# 06_rng.net
KiCad netlist of a schematic drawn in Altium Designer
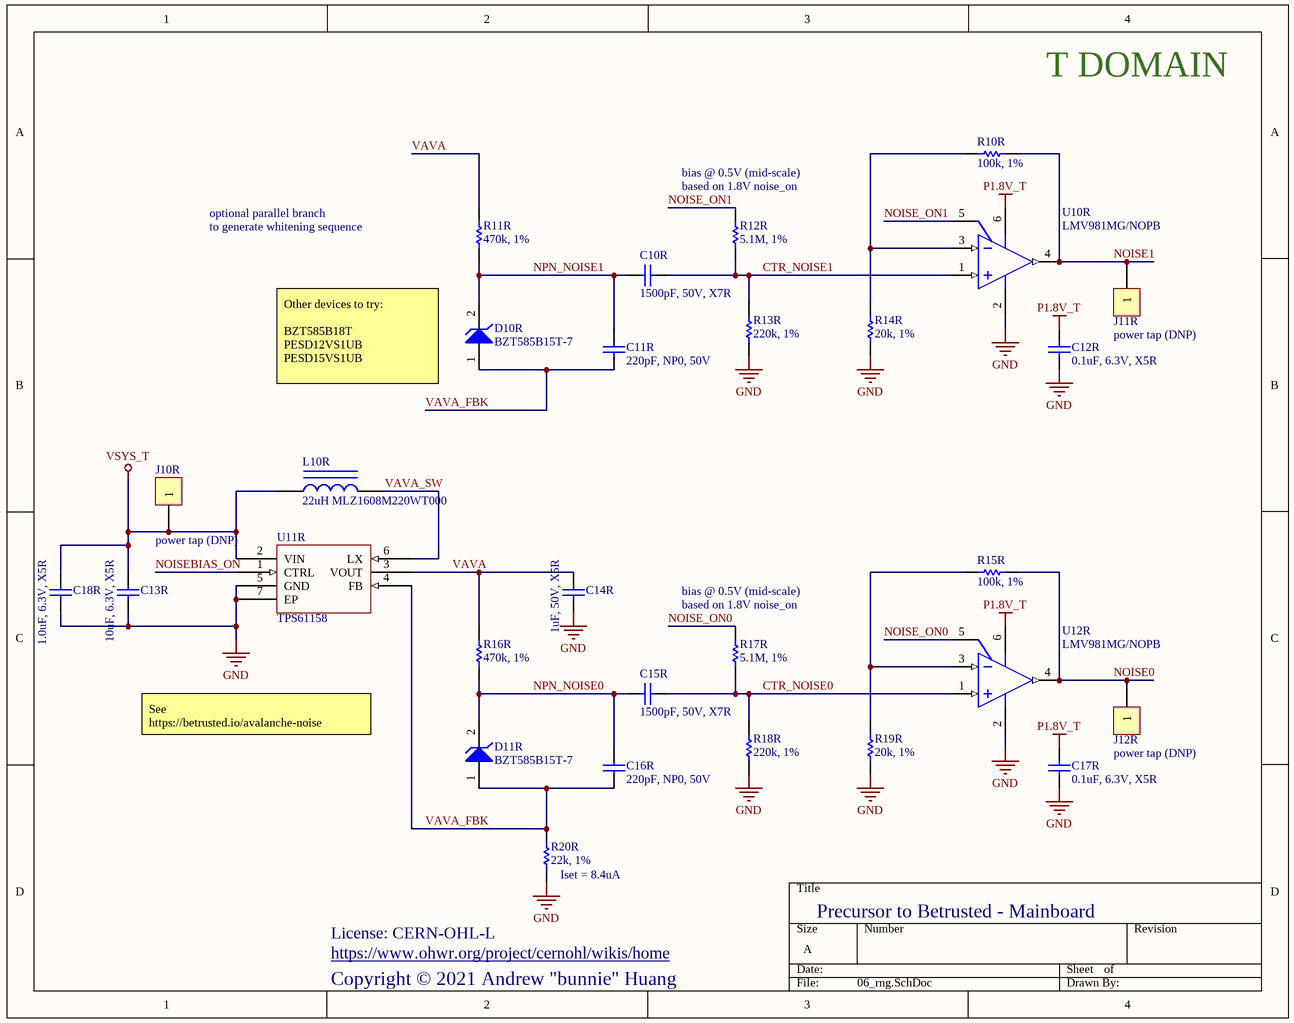
[diagram p0: 06_rng.SchDoc]

(export (version "E")
  (design (tool "Eeschema 10.0.6"))
  (components
    (comp (ref "C10R")
      (value "1500pF, 50V, X7R")
      (footprint "B_CAP0402")
      (description "Capacitor (Semiconductor SIM Model)")
      (fields (field (name "MPN") "CL05B152KB5NNNC"))
      (libsource (lib "Miscellaneous Devices") (part "Cap Semi"))
    )
    (comp (ref "C11R")
      (value "220pF, NP0, 50V")
      (footprint "B_CAP0402")
      (description "Capacitor (Semiconductor SIM Model)")
      (fields (field (name "MPN") "CL05C221JB5NNNC"))
      (libsource (lib "Miscellaneous Devices") (part "Cap Semi"))
    )
    (comp (ref "C12R")
      (value "0.1uF, 6.3V, X5R")
      (footprint "B_CAP0201")
      (description "Capacitor (Semiconductor SIM Model)")
      (fields (field (name "MPN") "CL03A104KQ3NNNC"))
      (libsource (lib "Miscellaneous Devices") (part "Cap Semi"))
    )
    (comp (ref "C13R")
      (value "10uF, 6.3V, X5R")
      (footprint "B_CAP0603")
      (description "Capacitor (Semiconductor SIM Model)")
      (fields (field (name "MPN") "CL10A106MQ8NNNC"))
      (libsource (lib "Miscellaneous Devices") (part "Cap Semi"))
    )
    (comp (ref "C14R")
      (value "1uF, 50V, X5R")
      (footprint "B_CAP0603")
      (description "Capacitor (Semiconductor SIM Model)")
      (fields (field (name "MPN") "CL10A105KB8NNNC"))
      (libsource (lib "Miscellaneous Devices") (part "Cap Semi"))
    )
    (comp (ref "C15R")
      (value "1500pF, 50V, X7R")
      (footprint "B_CAP0402")
      (description "Capacitor (Semiconductor SIM Model)")
      (fields (field (name "MPN") "CL05B152KB5NNNC"))
      (libsource (lib "Miscellaneous Devices") (part "Cap Semi"))
    )
    (comp (ref "C16R")
      (value "220pF, NP0, 50V")
      (footprint "B_CAP0402")
      (description "Capacitor (Semiconductor SIM Model)")
      (fields (field (name "MPN") "CL05C221JB5NNNC"))
      (libsource (lib "Miscellaneous Devices") (part "Cap Semi"))
    )
    (comp (ref "C17R")
      (value "0.1uF, 6.3V, X5R")
      (footprint "B_CAP0201")
      (description "Capacitor (Semiconductor SIM Model)")
      (fields (field (name "MPN") "CL03A104KQ3NNNC"))
      (libsource (lib "Miscellaneous Devices") (part "Cap Semi"))
    )
    (comp (ref "C18R")
      (value "1.0uF, 6.3V, X5R")
      (footprint "B_CAP0201")
      (description "Capacitor (Semiconductor SIM Model)")
      (fields (field (name "MPN") "GRM033R60J105MEA2D"))
      (libsource (lib "Miscellaneous Devices") (part "Cap Semi"))
    )
    (comp (ref "D10R")
      (value "BZT585B15T-7")
      (footprint "SOD523")
      (description "Zener Diode")
      (fields (field (name "PUBLISHER") "Altium Limited"))
      (libsource (lib "Miscellaneous Devices") (part "D Zener"))
    )
    (comp (ref "D11R")
      (value "BZT585B15T-7")
      (footprint "SOD523")
      (description "Zener Diode")
      (fields (field (name "PUBLISHER") "Altium Limited"))
      (libsource (lib "Miscellaneous Devices") (part "D Zener"))
    )
    (comp (ref "J10R")
      (value "power tap (DNP)")
      (footprint "B_PWRTAP0402")
      (description "Connector")
      (fields (field (name "MPN") "DNP"))
      (libsource (lib "") (part "CON1_1"))
    )
    (comp (ref "J11R")
      (value "power tap (DNP)")
      (footprint "B_PWRTAP0402")
      (description "Connector")
      (fields (field (name "MPN") "DNP"))
      (libsource (lib "*") (part "CON1"))
    )
    (comp (ref "J12R")
      (value "power tap (DNP)")
      (footprint "B_PWRTAP0402")
      (description "Connector")
      (fields (field (name "MPN") "DNP"))
      (libsource (lib "*") (part "CON1"))
    )
    (comp (ref "L10R")
      (value "22uH MLZ1608M220WT000")
      (footprint "INDC1608AN")
      (description "Magnetic-Core Inductor")
      (fields (field (name "MPN") "MLZ1608M220WT000"))
      (libsource (lib "Miscellaneous Devices") (part "Inductor Iron"))
    )
    (comp (ref "R10R")
      (value "100k, 1%")
      (footprint "B_RES0201")
      (description "Resistor")
      (fields (field (name "MPN") "ANY"))
      (libsource (lib "Miscellaneous Devices") (part "Res1"))
    )
    (comp (ref "R11R")
      (value "470k, 1%")
      (footprint "B_RES0402")
      (description "Resistor")
      (fields (field (name "MPN") "ANY"))
      (libsource (lib "Miscellaneous Devices") (part "Res1"))
    )
    (comp (ref "R12R")
      (value "5.1M, 1%")
      (footprint "B_RES0402")
      (description "Resistor")
      (fields (field (name "MPN") "RMCF0402FT5M10"))
      (libsource (lib "Miscellaneous Devices") (part "Res1"))
    )
    (comp (ref "R13R")
      (value "220k, 1%")
      (footprint "B_RES0201")
      (description "Resistor")
      (fields (field (name "MPN") "ANY"))
      (libsource (lib "Miscellaneous Devices") (part "Res1"))
    )
    (comp (ref "R14R")
      (value "20k, 1%")
      (footprint "B_RES0201")
      (description "Resistor")
      (fields (field (name "MPN") "ANY"))
      (libsource (lib "Miscellaneous Devices") (part "Res1"))
    )
    (comp (ref "R15R")
      (value "100k, 1%")
      (footprint "B_RES0201")
      (description "Resistor")
      (fields (field (name "MPN") "ANY"))
      (libsource (lib "Miscellaneous Devices") (part "Res1"))
    )
    (comp (ref "R16R")
      (value "470k, 1%")
      (footprint "B_RES0402")
      (description "Resistor")
      (fields (field (name "MPN") "ANY"))
      (libsource (lib "Miscellaneous Devices") (part "Res1"))
    )
    (comp (ref "R17R")
      (value "5.1M, 1%")
      (footprint "B_RES0402")
      (description "Resistor")
      (fields (field (name "MPN") "RMCF0402FT5M10"))
      (libsource (lib "Miscellaneous Devices") (part "Res1"))
    )
    (comp (ref "R18R")
      (value "220k, 1%")
      (footprint "B_RES0201")
      (description "Resistor")
      (fields (field (name "MPN") "ANY"))
      (libsource (lib "Miscellaneous Devices") (part "Res1"))
    )
    (comp (ref "R19R")
      (value "20k, 1%")
      (footprint "B_RES0201")
      (description "Resistor")
      (fields (field (name "MPN") "ANY"))
      (libsource (lib "Miscellaneous Devices") (part "Res1"))
    )
    (comp (ref "R20R")
      (value "22k, 1%")
      (footprint "B_RES0402")
      (description "Resistor")
      (fields (field (name "MPN") "ANY"))
      (libsource (lib "Miscellaneous Devices") (part "Res1"))
    )
    (comp (ref "U10R")
      (value "LMV981MG/NOPB")
      (footprint "DCK0006A_N")
      (description "Single 1.8V, RRIO Operational Amplifiers with Shutdown, 6-pin SC-70, Pb-Free")
      (libsource (lib "Altium Content Vault") (part "AMP-OPA-LMV981-6"))
    )
    (comp (ref "U11R")
      (value "TPS61158")
      (footprint "SON65P200X80_HS-7N")
      (description "30V WLED driver with integrated power diode")
      (fields (field (name "MPN") "TPS61158DRVR"))
      (libsource (lib "commonsch-new") (part "TPS61158"))
    )
    (comp (ref "U12R")
      (value "LMV981MG/NOPB")
      (footprint "DCK0006A_N")
      (description "Single 1.8V, RRIO Operational Amplifiers with Shutdown, 6-pin SC-70, Pb-Free")
      (libsource (lib "Altium Content Vault") (part "AMP-OPA-LMV981-6"))
    )
  )
  (nets
    (net (code "1") (name "/CTR_NOISE0") (class "Default")
      (node (ref "C15R") (pin "2") (pinfunction "2_2") (pintype "passive"))
      (node (ref "R17R") (pin "1") (pinfunction "1_1") (pintype "passive"))
      (node (ref "R18R") (pin "2") (pinfunction "2_2") (pintype "passive"))
      (node (ref "U12R") (pin "1") (pinfunction "IN+_1") (pintype "input"))
    )
    (net (code "2") (name "/CTR_NOISE1") (class "Default")
      (node (ref "C10R") (pin "2") (pinfunction "2_2") (pintype "passive"))
      (node (ref "R12R") (pin "1") (pinfunction "1_1") (pintype "passive"))
      (node (ref "R13R") (pin "2") (pinfunction "2_2") (pintype "passive"))
      (node (ref "U10R") (pin "1") (pinfunction "IN+_1") (pintype "input"))
    )
    (net (code "3") (name "/NOISE0") (class "Default")
      (node (ref "J12R") (pin "1") (pinfunction "1_1") (pintype "passive"))
      (node (ref "R15R") (pin "1") (pinfunction "1_1") (pintype "passive"))
      (node (ref "U12R") (pin "4") (pinfunction "OUT_4") (pintype "output"))
    )
    (net (code "4") (name "/NOISE1") (class "Default")
      (node (ref "J11R") (pin "1") (pinfunction "1_1") (pintype "passive"))
      (node (ref "R10R") (pin "1") (pinfunction "1_1") (pintype "passive"))
      (node (ref "U10R") (pin "4") (pinfunction "OUT_4") (pintype "output"))
    )
    (net (code "5") (name "/NOISEBIAS_ON") (class "Default")
      (node (ref "U11R") (pin "1") (pinfunction "CTRL_1") (pintype "input"))
    )
    (net (code "6") (name "/NOISE_ON0") (class "Default")
      (node (ref "R17R") (pin "2") (pinfunction "2_2") (pintype "passive"))
      (node (ref "U12R") (pin "5") (pinfunction "~{SHDN}_5") (pintype "passive"))
    )
    (net (code "7") (name "/NOISE_ON1") (class "Default")
      (node (ref "R12R") (pin "2") (pinfunction "2_2") (pintype "passive"))
      (node (ref "U10R") (pin "5") (pinfunction "~{SHDN}_5") (pintype "passive"))
    )
    (net (code "8") (name "/NPN_NOISE0") (class "Default")
      (node (ref "C15R") (pin "1") (pinfunction "1_1") (pintype "passive"))
      (node (ref "C16R") (pin "2") (pinfunction "2_2") (pintype "passive"))
      (node (ref "D11R") (pin "2") (pinfunction "K_2") (pintype "passive"))
      (node (ref "R16R") (pin "1") (pinfunction "1_1") (pintype "passive"))
    )
    (net (code "9") (name "/NPN_NOISE1") (class "Default")
      (node (ref "C10R") (pin "1") (pinfunction "1_1") (pintype "passive"))
      (node (ref "C11R") (pin "2") (pinfunction "2_2") (pintype "passive"))
      (node (ref "D10R") (pin "2") (pinfunction "K_2") (pintype "passive"))
      (node (ref "R11R") (pin "1") (pinfunction "1_1") (pintype "passive"))
    )
    (net (code "10") (name "/VAVA") (class "Default")
      (node (ref "C14R") (pin "1") (pinfunction "1_1") (pintype "passive"))
      (node (ref "R11R") (pin "2") (pinfunction "2_2") (pintype "passive"))
      (node (ref "R16R") (pin "2") (pinfunction "2_2") (pintype "passive"))
      (node (ref "U11R") (pin "3") (pinfunction "VOUT_3") (pintype "power_in"))
    )
    (net (code "11") (name "/VAVA_FBK") (class "Default")
      (node (ref "C11R") (pin "1") (pinfunction "1_1") (pintype "passive"))
      (node (ref "C16R") (pin "1") (pinfunction "1_1") (pintype "passive"))
      (node (ref "D10R") (pin "1") (pinfunction "A_1") (pintype "passive"))
      (node (ref "D11R") (pin "1") (pinfunction "A_1") (pintype "passive"))
      (node (ref "R20R") (pin "2") (pinfunction "2_2") (pintype "passive"))
      (node (ref "U11R") (pin "4") (pinfunction "FB_4") (pintype "input"))
    )
    (net (code "12") (name "/VAVA_SW") (class "Default")
      (node (ref "L10R") (pin "2") (pinfunction "2_2") (pintype "passive"))
      (node (ref "U11R") (pin "6") (pinfunction "LX_6") (pintype "input"))
    )
    (net (code "13") (name "GND") (class "Default")
      (node (ref "C12R") (pin "1") (pinfunction "1_1") (pintype "passive"))
      (node (ref "C13R") (pin "2") (pinfunction "2_2") (pintype "passive"))
      (node (ref "C14R") (pin "2") (pinfunction "2_2") (pintype "passive"))
      (node (ref "C17R") (pin "1") (pinfunction "1_1") (pintype "passive"))
      (node (ref "C18R") (pin "1") (pinfunction "1_1") (pintype "passive"))
      (node (ref "R13R") (pin "1") (pinfunction "1_1") (pintype "passive"))
      (node (ref "R14R") (pin "1") (pinfunction "1_1") (pintype "passive"))
      (node (ref "R18R") (pin "1") (pinfunction "1_1") (pintype "passive"))
      (node (ref "R19R") (pin "1") (pinfunction "1_1") (pintype "passive"))
      (node (ref "R20R") (pin "1") (pinfunction "1_1") (pintype "passive"))
      (node (ref "U10R") (pin "2") (pinfunction "GND_2") (pintype "power_in"))
      (node (ref "U11R") (pin "5") (pinfunction "GND_5") (pintype "power_in"))
      (node (ref "U11R") (pin "7") (pinfunction "EP_7") (pintype "power_in"))
      (node (ref "U12R") (pin "2") (pinfunction "GND_2") (pintype "power_in"))
    )
    (net (code "14") (name "Net-(U10R-IN-)") (class "Default")
      (node (ref "R10R") (pin "2") (pinfunction "2_2") (pintype "passive"))
      (node (ref "R14R") (pin "2") (pinfunction "2_2") (pintype "passive"))
      (node (ref "U10R") (pin "3") (pinfunction "IN-_3") (pintype "input"))
    )
    (net (code "15") (name "Net-(U12R-IN-)") (class "Default")
      (node (ref "R15R") (pin "2") (pinfunction "2_2") (pintype "passive"))
      (node (ref "R19R") (pin "2") (pinfunction "2_2") (pintype "passive"))
      (node (ref "U12R") (pin "3") (pinfunction "IN-_3") (pintype "input"))
    )
    (net (code "16") (name "P1.8V_T") (class "Default")
      (node (ref "C12R") (pin "2") (pinfunction "2_2") (pintype "passive"))
      (node (ref "C17R") (pin "2") (pinfunction "2_2") (pintype "passive"))
      (node (ref "U10R") (pin "6") (pinfunction "VDD_6") (pintype "power_in"))
      (node (ref "U12R") (pin "6") (pinfunction "VDD_6") (pintype "power_in"))
    )
    (net (code "17") (name "VSYS_T") (class "Default")
      (node (ref "C13R") (pin "1") (pinfunction "1_1") (pintype "passive"))
      (node (ref "C18R") (pin "2") (pinfunction "2_2") (pintype "passive"))
      (node (ref "J10R") (pin "1") (pinfunction "1_1") (pintype "passive"))
      (node (ref "L10R") (pin "1") (pinfunction "1_1") (pintype "passive"))
      (node (ref "U11R") (pin "2") (pinfunction "VIN_2") (pintype "power_in"))
    )
  )
)
